# folimetro_pcb.net
KiCad netlist of a schematic drawn in EAGLE
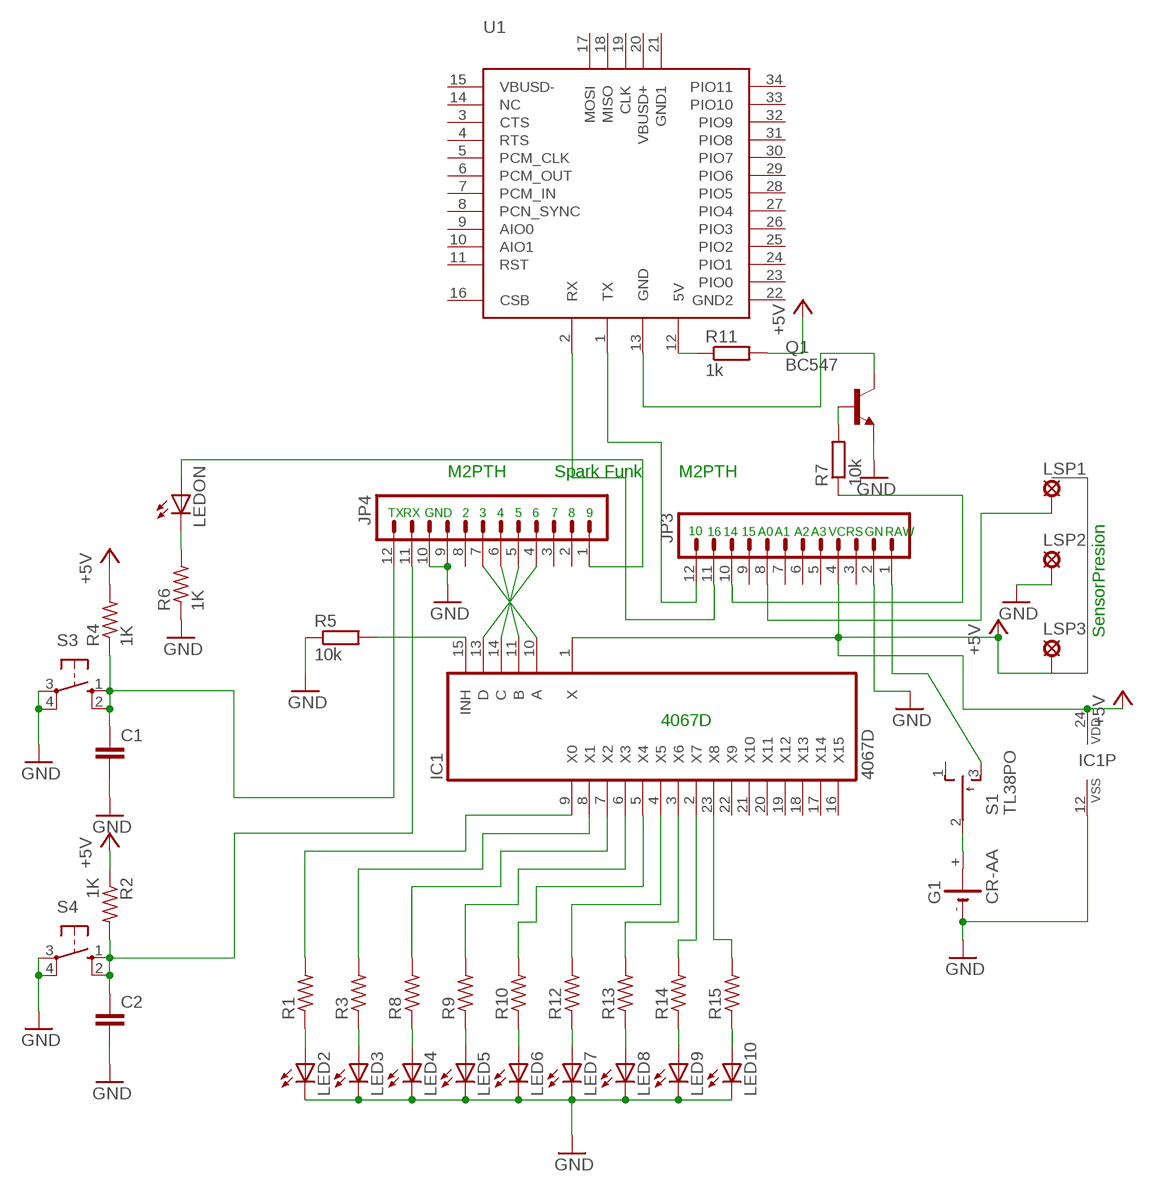
[diagram p0: schematic, sheet 1]

(export (version "E")
  (design (tool "Eeschema 10.0.6"))
  (components
    (comp (ref "C1")
      (value "C-EUC1206K")
      (footprint "eagle-import:C1206K")
      (libsource (lib "eagle-import") (part "C-EUC1206K"))
    )
    (comp (ref "C2")
      (value "C-EUC1206K")
      (footprint "eagle-import:C1206K")
      (libsource (lib "eagle-import") (part "C-EUC1206K"))
    )
    (comp (ref "G1")
      (value "CR-AA")
      (footprint "eagle-import:CRAA")
      (libsource (lib "eagle-import") (part "CR-AA"))
    )
    (comp (ref "IC1")
      (value "4067D")
      (footprint "eagle-import:SO24W")
      (libsource (lib "eagle-import") (part "4067D"))
    )
    (comp (ref "JP3")
      (value "M12PTH")
      (footprint "eagle-import:1X12")
      (libsource (lib "eagle-import") (part "M12PTH"))
    )
    (comp (ref "JP4")
      (value "M12PTH")
      (footprint "eagle-import:1X12")
      (libsource (lib "eagle-import") (part "M12PTH"))
    )
    (comp (ref "LED2")
      (value "LED3MM")
      (footprint "eagle-import:LED3MM")
      (libsource (lib "eagle-import") (part "LED3MM"))
    )
    (comp (ref "LED3")
      (value "LED3MM")
      (footprint "eagle-import:LED3MM")
      (libsource (lib "eagle-import") (part "LED3MM"))
    )
    (comp (ref "LED4")
      (value "LED3MM")
      (footprint "eagle-import:LED3MM")
      (libsource (lib "eagle-import") (part "LED3MM"))
    )
    (comp (ref "LED5")
      (value "LED3MM")
      (footprint "eagle-import:LED3MM")
      (libsource (lib "eagle-import") (part "LED3MM"))
    )
    (comp (ref "LED6")
      (value "LED3MM")
      (footprint "eagle-import:LED3MM")
      (libsource (lib "eagle-import") (part "LED3MM"))
    )
    (comp (ref "LED7")
      (value "LED3MM")
      (footprint "eagle-import:LED3MM")
      (libsource (lib "eagle-import") (part "LED3MM"))
    )
    (comp (ref "LED8")
      (value "LED3MM")
      (footprint "eagle-import:LED3MM")
      (libsource (lib "eagle-import") (part "LED3MM"))
    )
    (comp (ref "LED9")
      (value "LED3MM")
      (footprint "eagle-import:LED3MM")
      (libsource (lib "eagle-import") (part "LED3MM"))
    )
    (comp (ref "LED10")
      (value "LED3MM")
      (footprint "eagle-import:LED3MM")
      (libsource (lib "eagle-import") (part "LED3MM"))
    )
    (comp (ref "LEDON")
      (value "LED3MM")
      (footprint "eagle-import:LED3MM")
      (libsource (lib "eagle-import") (part "LED3MM"))
    )
    (comp (ref "LSP1")
      (value "SE13")
      (footprint "eagle-import:SE13")
      (libsource (lib "eagle-import") (part "SE13"))
    )
    (comp (ref "LSP2")
      (value "SE13")
      (footprint "eagle-import:SE13")
      (libsource (lib "eagle-import") (part "SE13"))
    )
    (comp (ref "LSP3")
      (value "SE13")
      (footprint "eagle-import:SE13")
      (libsource (lib "eagle-import") (part "SE13"))
    )
    (comp (ref "Q1")
      (value "BC547")
      (footprint "eagle-import:SOT23")
      (libsource (lib "eagle-import") (part "BC848SMDALT1"))
    )
    (comp (ref "R1")
      (value "R-US_R1206")
      (footprint "eagle-import:R1206")
      (libsource (lib "eagle-import") (part "R-US_R1206"))
    )
    (comp (ref "R2")
      (value "1K")
      (footprint "eagle-import:R1206")
      (libsource (lib "eagle-import") (part "R-US_R1206"))
    )
    (comp (ref "R3")
      (value "R-US_R1206")
      (footprint "eagle-import:R1206")
      (libsource (lib "eagle-import") (part "R-US_R1206"))
    )
    (comp (ref "R4")
      (value "1K")
      (footprint "eagle-import:R1206")
      (libsource (lib "eagle-import") (part "R-US_R1206"))
    )
    (comp (ref "R5")
      (value "10k")
      (footprint "eagle-import:R1206")
      (libsource (lib "eagle-import") (part "R-EU_R1206"))
    )
    (comp (ref "R6")
      (value "1K")
      (footprint "eagle-import:R1206")
      (libsource (lib "eagle-import") (part "R-US_R1206"))
    )
    (comp (ref "R7")
      (value "10k")
      (footprint "eagle-import:R1206")
      (libsource (lib "eagle-import") (part "R-EU_R1206"))
    )
    (comp (ref "R8")
      (value "R-US_R1206")
      (footprint "eagle-import:R1206")
      (libsource (lib "eagle-import") (part "R-US_R1206"))
    )
    (comp (ref "R9")
      (value "R-US_R1206")
      (footprint "eagle-import:R1206")
      (libsource (lib "eagle-import") (part "R-US_R1206"))
    )
    (comp (ref "R10")
      (value "R-US_R1206")
      (footprint "eagle-import:R1206")
      (libsource (lib "eagle-import") (part "R-US_R1206"))
    )
    (comp (ref "R11")
      (value "1k")
      (footprint "eagle-import:R1206")
      (libsource (lib "eagle-import") (part "R-EU_R1206"))
    )
    (comp (ref "R12")
      (value "R-US_R1206")
      (footprint "eagle-import:R1206")
      (libsource (lib "eagle-import") (part "R-US_R1206"))
    )
    (comp (ref "R13")
      (value "R-US_R1206")
      (footprint "eagle-import:R1206")
      (libsource (lib "eagle-import") (part "R-US_R1206"))
    )
    (comp (ref "R14")
      (value "R-US_R1206")
      (footprint "eagle-import:R1206")
      (libsource (lib "eagle-import") (part "R-US_R1206"))
    )
    (comp (ref "R15")
      (value "R-US_R1206")
      (footprint "eagle-import:R1206")
      (libsource (lib "eagle-import") (part "R-US_R1206"))
    )
    (comp (ref "S1")
      (value "TL38PO")
      (footprint "eagle-import:TL3XPO")
      (libsource (lib "eagle-import") (part "TL38PO"))
    )
    (comp (ref "S3")
      (value "10-XX")
      (footprint "eagle-import:B3F-10XX")
      (fields (field (name "MPN") "B3F-1000"))
      (libsource (lib "eagle-import") (part "10-XX"))
    )
    (comp (ref "S4")
      (value "10-XX")
      (footprint "eagle-import:B3F-10XX")
      (fields (field (name "MPN") "B3F-1000"))
      (libsource (lib "eagle-import") (part "10-XX"))
    )
    (comp (ref "U1")
      (value "HC_05")
      (footprint "eagle-import:BLUETOOTH_SMD")
      (libsource (lib "eagle-import") (part "HC_05"))
    )
  )
  (nets
    (net (code "1") (name "+5V") (class "Default")
      (node (ref "IC1") (pin "1") (pinfunction "X_1") (pintype "output"))
      (node (ref "IC1") (pin "24") (pinfunction "VDD_24") (pintype "power_in"))
      (node (ref "JP3") (pin "4") (pinfunction "4_4") (pintype "passive"))
      (node (ref "LSP3") (pin "MP") (pinfunction "MP_MP") (pintype "passive"))
      (node (ref "R11") (pin "2") (pinfunction "2_2") (pintype "passive"))
      (node (ref "R2") (pin "1") (pinfunction "1_1") (pintype "passive"))
      (node (ref "R4") (pin "2") (pinfunction "2_2") (pintype "passive"))
    )
    (net (code "2") (name "GND") (class "Default")
      (node (ref "C1") (pin "2") (pinfunction "2_2") (pintype "passive"))
      (node (ref "C2") (pin "2") (pinfunction "2_2") (pintype "passive"))
      (node (ref "G1") (pin "-") (pinfunction "-_-") (pintype "passive"))
      (node (ref "IC1") (pin "12") (pinfunction "VSS_12") (pintype "power_in"))
      (node (ref "JP3") (pin "2") (pinfunction "2_2") (pintype "passive"))
      (node (ref "JP4") (pin "10") (pinfunction "10_10") (pintype "passive"))
      (node (ref "JP4") (pin "9") (pinfunction "9_9") (pintype "passive"))
      (node (ref "LED10") (pin "K") (pinfunction "C_K") (pintype "passive"))
      (node (ref "LED2") (pin "K") (pinfunction "C_K") (pintype "passive"))
      (node (ref "LED3") (pin "K") (pinfunction "C_K") (pintype "passive"))
      (node (ref "LED4") (pin "K") (pinfunction "C_K") (pintype "passive"))
      (node (ref "LED5") (pin "K") (pinfunction "C_K") (pintype "passive"))
      (node (ref "LED6") (pin "K") (pinfunction "C_K") (pintype "passive"))
      (node (ref "LED7") (pin "K") (pinfunction "C_K") (pintype "passive"))
      (node (ref "LED8") (pin "K") (pinfunction "C_K") (pintype "passive"))
      (node (ref "LED9") (pin "K") (pinfunction "C_K") (pintype "passive"))
      (node (ref "LSP2") (pin "MP") (pinfunction "MP_MP") (pintype "passive"))
      (node (ref "Q1") (pin "2") (pinfunction "E_2") (pintype "passive"))
      (node (ref "R5") (pin "1") (pinfunction "1_1") (pintype "passive"))
      (node (ref "R6") (pin "1") (pinfunction "1_1") (pintype "passive"))
      (node (ref "S3") (pin "3") (pinfunction "P_3") (pintype "passive"))
      (node (ref "S3") (pin "4") (pinfunction "P1_4") (pintype "passive"))
      (node (ref "S4") (pin "3") (pinfunction "P_3") (pintype "passive"))
      (node (ref "S4") (pin "4") (pinfunction "P1_4") (pintype "passive"))
    )
    (net (code "3") (name "Net-(IC1A-A)") (class "Default")
      (node (ref "IC1") (pin "10") (pinfunction "A_10") (pintype "input"))
      (node (ref "JP4") (pin "7") (pinfunction "7_7") (pintype "passive"))
    )
    (net (code "4") (name "Net-(IC1A-B)") (class "Default")
      (node (ref "IC1") (pin "11") (pinfunction "B_11") (pintype "input"))
      (node (ref "JP4") (pin "6") (pinfunction "6_6") (pintype "passive"))
    )
    (net (code "5") (name "Net-(IC1A-C)") (class "Default")
      (node (ref "IC1") (pin "14") (pinfunction "C_14") (pintype "input"))
      (node (ref "JP4") (pin "5") (pinfunction "5_5") (pintype "passive"))
    )
    (net (code "6") (name "Net-(IC1A-D)") (class "Default")
      (node (ref "IC1") (pin "13") (pinfunction "D_13") (pintype "input"))
      (node (ref "JP4") (pin "4") (pinfunction "4_4") (pintype "passive"))
    )
    (net (code "7") (name "Net-(IC1A-INH)") (class "Default")
      (node (ref "IC1") (pin "15") (pinfunction "INH_15") (pintype "input"))
      (node (ref "R5") (pin "2") (pinfunction "2_2") (pintype "passive"))
    )
    (net (code "8") (name "Net-(IC1A-X0)") (class "Default")
      (node (ref "IC1") (pin "9") (pinfunction "X0_9") (pintype "input"))
      (node (ref "R1") (pin "2") (pinfunction "2_2") (pintype "passive"))
    )
    (net (code "9") (name "Net-(IC1A-X1)") (class "Default")
      (node (ref "IC1") (pin "8") (pinfunction "X1_8") (pintype "input"))
      (node (ref "R3") (pin "2") (pinfunction "2_2") (pintype "passive"))
    )
    (net (code "10") (name "Net-(IC1A-X2)") (class "Default")
      (node (ref "IC1") (pin "7") (pinfunction "X2_7") (pintype "input"))
      (node (ref "R8") (pin "2") (pinfunction "2_2") (pintype "passive"))
    )
    (net (code "11") (name "Net-(IC1A-X3)") (class "Default")
      (node (ref "IC1") (pin "6") (pinfunction "X3_6") (pintype "input"))
      (node (ref "R9") (pin "2") (pinfunction "2_2") (pintype "passive"))
    )
    (net (code "12") (name "Net-(IC1A-X4)") (class "Default")
      (node (ref "IC1") (pin "5") (pinfunction "X4_5") (pintype "input"))
      (node (ref "R10") (pin "2") (pinfunction "2_2") (pintype "passive"))
    )
    (net (code "13") (name "Net-(IC1A-X5)") (class "Default")
      (node (ref "IC1") (pin "4") (pinfunction "X5_4") (pintype "input"))
      (node (ref "R12") (pin "2") (pinfunction "2_2") (pintype "passive"))
    )
    (net (code "14") (name "Net-(IC1A-X6)") (class "Default")
      (node (ref "IC1") (pin "3") (pinfunction "X6_3") (pintype "input"))
      (node (ref "R13") (pin "2") (pinfunction "2_2") (pintype "passive"))
    )
    (net (code "15") (name "Net-(IC1A-X7)") (class "Default")
      (node (ref "IC1") (pin "2") (pinfunction "X7_2") (pintype "input"))
      (node (ref "R14") (pin "2") (pinfunction "2_2") (pintype "passive"))
    )
    (net (code "16") (name "Net-(IC1A-X8)") (class "Default")
      (node (ref "IC1") (pin "23") (pinfunction "X8_23") (pintype "input"))
      (node (ref "R15") (pin "2") (pinfunction "2_2") (pintype "passive"))
    )
    (net (code "17") (name "Net-(JP3-Pad8)") (class "Default")
      (node (ref "JP3") (pin "8") (pinfunction "8_8") (pintype "passive"))
      (node (ref "LSP1") (pin "MP") (pinfunction "MP_MP") (pintype "passive"))
    )
    (net (code "18") (name "Net-(JP3-Pad10)") (class "Default")
      (node (ref "JP3") (pin "10") (pinfunction "10_10") (pintype "passive"))
      (node (ref "R7") (pin "1") (pinfunction "1_1") (pintype "passive"))
    )
    (net (code "19") (name "Net-(JP4-Pad1)") (class "Default")
      (node (ref "JP4") (pin "1") (pinfunction "1_1") (pintype "passive"))
      (node (ref "LEDON") (pin "A") (pinfunction "A_A") (pintype "passive"))
    )
    (net (code "20") (name "Net-(LED2-PadA)") (class "Default")
      (node (ref "LED2") (pin "A") (pinfunction "A_A") (pintype "passive"))
      (node (ref "R1") (pin "1") (pinfunction "1_1") (pintype "passive"))
    )
    (net (code "21") (name "Net-(LED3-PadA)") (class "Default")
      (node (ref "LED3") (pin "A") (pinfunction "A_A") (pintype "passive"))
      (node (ref "R3") (pin "1") (pinfunction "1_1") (pintype "passive"))
    )
    (net (code "22") (name "Net-(LED4-PadA)") (class "Default")
      (node (ref "LED4") (pin "A") (pinfunction "A_A") (pintype "passive"))
      (node (ref "R8") (pin "1") (pinfunction "1_1") (pintype "passive"))
    )
    (net (code "23") (name "Net-(LED5-PadA)") (class "Default")
      (node (ref "LED5") (pin "A") (pinfunction "A_A") (pintype "passive"))
      (node (ref "R9") (pin "1") (pinfunction "1_1") (pintype "passive"))
    )
    (net (code "24") (name "Net-(LED6-PadA)") (class "Default")
      (node (ref "LED6") (pin "A") (pinfunction "A_A") (pintype "passive"))
      (node (ref "R10") (pin "1") (pinfunction "1_1") (pintype "passive"))
    )
    (net (code "25") (name "Net-(LED7-PadA)") (class "Default")
      (node (ref "LED7") (pin "A") (pinfunction "A_A") (pintype "passive"))
      (node (ref "R12") (pin "1") (pinfunction "1_1") (pintype "passive"))
    )
    (net (code "26") (name "Net-(LED8-PadA)") (class "Default")
      (node (ref "LED8") (pin "A") (pinfunction "A_A") (pintype "passive"))
      (node (ref "R13") (pin "1") (pinfunction "1_1") (pintype "passive"))
    )
    (net (code "27") (name "Net-(LED9-PadA)") (class "Default")
      (node (ref "LED9") (pin "A") (pinfunction "A_A") (pintype "passive"))
      (node (ref "R14") (pin "1") (pinfunction "1_1") (pintype "passive"))
    )
    (net (code "28") (name "Net-(LED10-PadA)") (class "Default")
      (node (ref "LED10") (pin "A") (pinfunction "A_A") (pintype "passive"))
      (node (ref "R15") (pin "1") (pinfunction "1_1") (pintype "passive"))
    )
    (net (code "29") (name "Net-(LEDON-C)") (class "Default")
      (node (ref "LEDON") (pin "K") (pinfunction "C_K") (pintype "passive"))
      (node (ref "R6") (pin "2") (pinfunction "2_2") (pintype "passive"))
    )
    (net (code "30") (name "Net-(Q1-B)") (class "Default")
      (node (ref "Q1") (pin "1") (pinfunction "B_1") (pintype "passive"))
      (node (ref "R7") (pin "2") (pinfunction "2_2") (pintype "passive"))
    )
    (net (code "31") (name "Net-(Q1-C)") (class "Default")
      (node (ref "Q1") (pin "3") (pinfunction "C_3") (pintype "passive"))
      (node (ref "U1") (pin "13") (pinfunction "GND_13") (pintype "bidirectional"))
    )
    (net (code "32") (name "Net-(S1-P)") (class "Default")
      (node (ref "G1") (pin "+") (pinfunction "+_+") (pintype "passive"))
      (node (ref "S1") (pin "2") (pinfunction "P_2") (pintype "passive"))
    )
    (net (code "33") (name "Net-(S1-S)") (class "Default")
      (node (ref "JP3") (pin "1") (pinfunction "1_1") (pintype "passive"))
      (node (ref "S1") (pin "3") (pinfunction "S_3") (pintype "passive"))
    )
    (net (code "34") (name "Net-(S3-S)") (class "Default")
      (node (ref "C1") (pin "1") (pinfunction "1_1") (pintype "passive"))
      (node (ref "JP4") (pin "12") (pinfunction "12_12") (pintype "passive"))
      (node (ref "R4") (pin "1") (pinfunction "1_1") (pintype "passive"))
      (node (ref "S3") (pin "1") (pinfunction "S_1") (pintype "passive"))
      (node (ref "S3") (pin "2") (pinfunction "S1_2") (pintype "passive"))
    )
    (net (code "35") (name "Net-(S4-S)") (class "Default")
      (node (ref "C2") (pin "1") (pinfunction "1_1") (pintype "passive"))
      (node (ref "JP4") (pin "11") (pinfunction "11_11") (pintype "passive"))
      (node (ref "R2") (pin "2") (pinfunction "2_2") (pintype "passive"))
      (node (ref "S4") (pin "1") (pinfunction "S_1") (pintype "passive"))
      (node (ref "S4") (pin "2") (pinfunction "S1_2") (pintype "passive"))
    )
    (net (code "36") (name "Net-(U1-5V)") (class "Default")
      (node (ref "R11") (pin "1") (pinfunction "1_1") (pintype "passive"))
      (node (ref "U1") (pin "12") (pinfunction "5V_12") (pintype "power_in"))
    )
    (net (code "37") (name "Net-(U1-RX)") (class "Default")
      (node (ref "JP3") (pin "11") (pinfunction "11_11") (pintype "passive"))
      (node (ref "U1") (pin "2") (pinfunction "RX_2") (pintype "bidirectional"))
    )
    (net (code "38") (name "Net-(U1-TX)") (class "Default")
      (node (ref "JP3") (pin "12") (pinfunction "12_12") (pintype "passive"))
      (node (ref "U1") (pin "1") (pinfunction "TX_1") (pintype "bidirectional"))
    )
    (net (code "39") (name "unconnected-(G1-+-Pad+@1)") (class "Default")
      (node (ref "G1") (pin "+@1") (pinfunction "+_+@1") (pintype "passive"))
    )
    (net (code "40") (name "unconnected-(IC1A-X9-Pad22)") (class "Default")
      (node (ref "IC1") (pin "22") (pinfunction "X9_22") (pintype "input"))
    )
    (net (code "41") (name "unconnected-(IC1A-X10-Pad21)") (class "Default")
      (node (ref "IC1") (pin "21") (pinfunction "X10_21") (pintype "input"))
    )
    (net (code "42") (name "unconnected-(IC1A-X11-Pad20)") (class "Default")
      (node (ref "IC1") (pin "20") (pinfunction "X11_20") (pintype "input"))
    )
    (net (code "43") (name "unconnected-(IC1A-X12-Pad19)") (class "Default")
      (node (ref "IC1") (pin "19") (pinfunction "X12_19") (pintype "input"))
    )
    (net (code "44") (name "unconnected-(IC1A-X13-Pad18)") (class "Default")
      (node (ref "IC1") (pin "18") (pinfunction "X13_18") (pintype "input"))
    )
    (net (code "45") (name "unconnected-(IC1A-X14-Pad17)") (class "Default")
      (node (ref "IC1") (pin "17") (pinfunction "X14_17") (pintype "input"))
    )
    (net (code "46") (name "unconnected-(IC1A-X15-Pad16)") (class "Default")
      (node (ref "IC1") (pin "16") (pinfunction "X15_16") (pintype "input"))
    )
    (net (code "47") (name "unconnected-(JP3-Pad3)") (class "Default")
      (node (ref "JP3") (pin "3") (pinfunction "3_3") (pintype "passive"))
    )
    (net (code "48") (name "unconnected-(JP3-Pad5)") (class "Default")
      (node (ref "JP3") (pin "5") (pinfunction "5_5") (pintype "passive"))
    )
    (net (code "49") (name "unconnected-(JP3-Pad6)") (class "Default")
      (node (ref "JP3") (pin "6") (pinfunction "6_6") (pintype "passive"))
    )
    (net (code "50") (name "unconnected-(JP3-Pad7)") (class "Default")
      (node (ref "JP3") (pin "7") (pinfunction "7_7") (pintype "passive"))
    )
    (net (code "51") (name "unconnected-(JP3-Pad9)") (class "Default")
      (node (ref "JP3") (pin "9") (pinfunction "9_9") (pintype "passive"))
    )
    (net (code "52") (name "unconnected-(JP4-Pad2)") (class "Default")
      (node (ref "JP4") (pin "2") (pinfunction "2_2") (pintype "passive"))
    )
    (net (code "53") (name "unconnected-(JP4-Pad3)") (class "Default")
      (node (ref "JP4") (pin "3") (pinfunction "3_3") (pintype "passive"))
    )
    (net (code "54") (name "unconnected-(JP4-Pad8)") (class "Default")
      (node (ref "JP4") (pin "8") (pinfunction "8_8") (pintype "passive"))
    )
    (net (code "55") (name "unconnected-(S1-O-Pad1)") (class "Default")
      (node (ref "S1") (pin "1") (pinfunction "O_1") (pintype "passive"))
    )
    (net (code "56") (name "unconnected-(U1-AIO0-Pad9)") (class "Default")
      (node (ref "U1") (pin "9") (pinfunction "AIO0_9") (pintype "bidirectional"))
    )
    (net (code "57") (name "unconnected-(U1-AIO1-Pad10)") (class "Default")
      (node (ref "U1") (pin "10") (pinfunction "AIO1_10") (pintype "bidirectional"))
    )
    (net (code "58") (name "unconnected-(U1-CLK-Pad19)") (class "Default")
      (node (ref "U1") (pin "19") (pinfunction "CLK_19") (pintype "bidirectional"))
    )
    (net (code "59") (name "unconnected-(U1-CSB-Pad16)") (class "Default")
      (node (ref "U1") (pin "16") (pinfunction "CSB_16") (pintype "bidirectional"))
    )
    (net (code "60") (name "unconnected-(U1-CTS-Pad3)") (class "Default")
      (node (ref "U1") (pin "3") (pinfunction "CTS_3") (pintype "bidirectional"))
    )
    (net (code "61") (name "unconnected-(U1-GND1-Pad21)") (class "Default")
      (node (ref "U1") (pin "21") (pinfunction "GND1_21") (pintype "bidirectional"))
    )
    (net (code "62") (name "unconnected-(U1-GND2-Pad22)") (class "Default")
      (node (ref "U1") (pin "22") (pinfunction "GND2_22") (pintype "bidirectional"))
    )
    (net (code "63") (name "unconnected-(U1-MISO-Pad18)") (class "Default")
      (node (ref "U1") (pin "18") (pinfunction "MISO_18") (pintype "bidirectional"))
    )
    (net (code "64") (name "unconnected-(U1-MOSI-Pad17)") (class "Default")
      (node (ref "U1") (pin "17") (pinfunction "MOSI_17") (pintype "bidirectional"))
    )
    (net (code "65") (name "unconnected-(U1-NC-Pad14)") (class "Default")
      (node (ref "U1") (pin "14") (pinfunction "NC_14") (pintype "bidirectional"))
    )
    (net (code "66") (name "unconnected-(U1-PCM_CLK-Pad5)") (class "Default")
      (node (ref "U1") (pin "5") (pinfunction "PCM_CLK_5") (pintype "bidirectional"))
    )
    (net (code "67") (name "unconnected-(U1-PCM_IN-Pad7)") (class "Default")
      (node (ref "U1") (pin "7") (pinfunction "PCM_IN_7") (pintype "bidirectional"))
    )
    (net (code "68") (name "unconnected-(U1-PCM_OUT-Pad6)") (class "Default")
      (node (ref "U1") (pin "6") (pinfunction "PCM_OUT_6") (pintype "bidirectional"))
    )
    (net (code "69") (name "unconnected-(U1-PCN_SYNC-Pad8)") (class "Default")
      (node (ref "U1") (pin "8") (pinfunction "PCN_SYNC_8") (pintype "bidirectional"))
    )
    (net (code "70") (name "unconnected-(U1-PIO0-Pad23)") (class "Default")
      (node (ref "U1") (pin "23") (pinfunction "PIO0_23") (pintype "bidirectional"))
    )
    (net (code "71") (name "unconnected-(U1-PIO1-Pad24)") (class "Default")
      (node (ref "U1") (pin "24") (pinfunction "PIO1_24") (pintype "bidirectional"))
    )
    (net (code "72") (name "unconnected-(U1-PIO2-Pad25)") (class "Default")
      (node (ref "U1") (pin "25") (pinfunction "PIO2_25") (pintype "bidirectional"))
    )
    (net (code "73") (name "unconnected-(U1-PIO3-Pad26)") (class "Default")
      (node (ref "U1") (pin "26") (pinfunction "PIO3_26") (pintype "bidirectional"))
    )
    (net (code "74") (name "unconnected-(U1-PIO4-Pad27)") (class "Default")
      (node (ref "U1") (pin "27") (pinfunction "PIO4_27") (pintype "bidirectional"))
    )
    (net (code "75") (name "unconnected-(U1-PIO5-Pad28)") (class "Default")
      (node (ref "U1") (pin "28") (pinfunction "PIO5_28") (pintype "bidirectional"))
    )
    (net (code "76") (name "unconnected-(U1-PIO6-Pad29)") (class "Default")
      (node (ref "U1") (pin "29") (pinfunction "PIO6_29") (pintype "bidirectional"))
    )
    (net (code "77") (name "unconnected-(U1-PIO7-Pad30)") (class "Default")
      (node (ref "U1") (pin "30") (pinfunction "PIO7_30") (pintype "bidirectional"))
    )
    (net (code "78") (name "unconnected-(U1-PIO8-Pad31)") (class "Default")
      (node (ref "U1") (pin "31") (pinfunction "PIO8_31") (pintype "bidirectional"))
    )
    (net (code "79") (name "unconnected-(U1-PIO9-Pad32)") (class "Default")
      (node (ref "U1") (pin "32") (pinfunction "PIO9_32") (pintype "bidirectional"))
    )
    (net (code "80") (name "unconnected-(U1-PIO10-Pad33)") (class "Default")
      (node (ref "U1") (pin "33") (pinfunction "PIO10_33") (pintype "bidirectional"))
    )
    (net (code "81") (name "unconnected-(U1-PIO11-Pad34)") (class "Default")
      (node (ref "U1") (pin "34") (pinfunction "PIO11_34") (pintype "bidirectional"))
    )
    (net (code "82") (name "unconnected-(U1-RST-Pad11)") (class "Default")
      (node (ref "U1") (pin "11") (pinfunction "RST_11") (pintype "bidirectional"))
    )
    (net (code "83") (name "unconnected-(U1-RTS-Pad4)") (class "Default")
      (node (ref "U1") (pin "4") (pinfunction "RTS_4") (pintype "bidirectional"))
    )
    (net (code "84") (name "unconnected-(U1-VBUSD+-Pad20)") (class "Default")
      (node (ref "U1") (pin "20") (pinfunction "VBUSD+_20") (pintype "bidirectional"))
    )
    (net (code "85") (name "unconnected-(U1-VBUSD--Pad15)") (class "Default")
      (node (ref "U1") (pin "15") (pinfunction "VBUSD-_15") (pintype "bidirectional"))
    )
  )
)
